# RTC.net
KiCad netlist of a schematic drawn in EAGLE
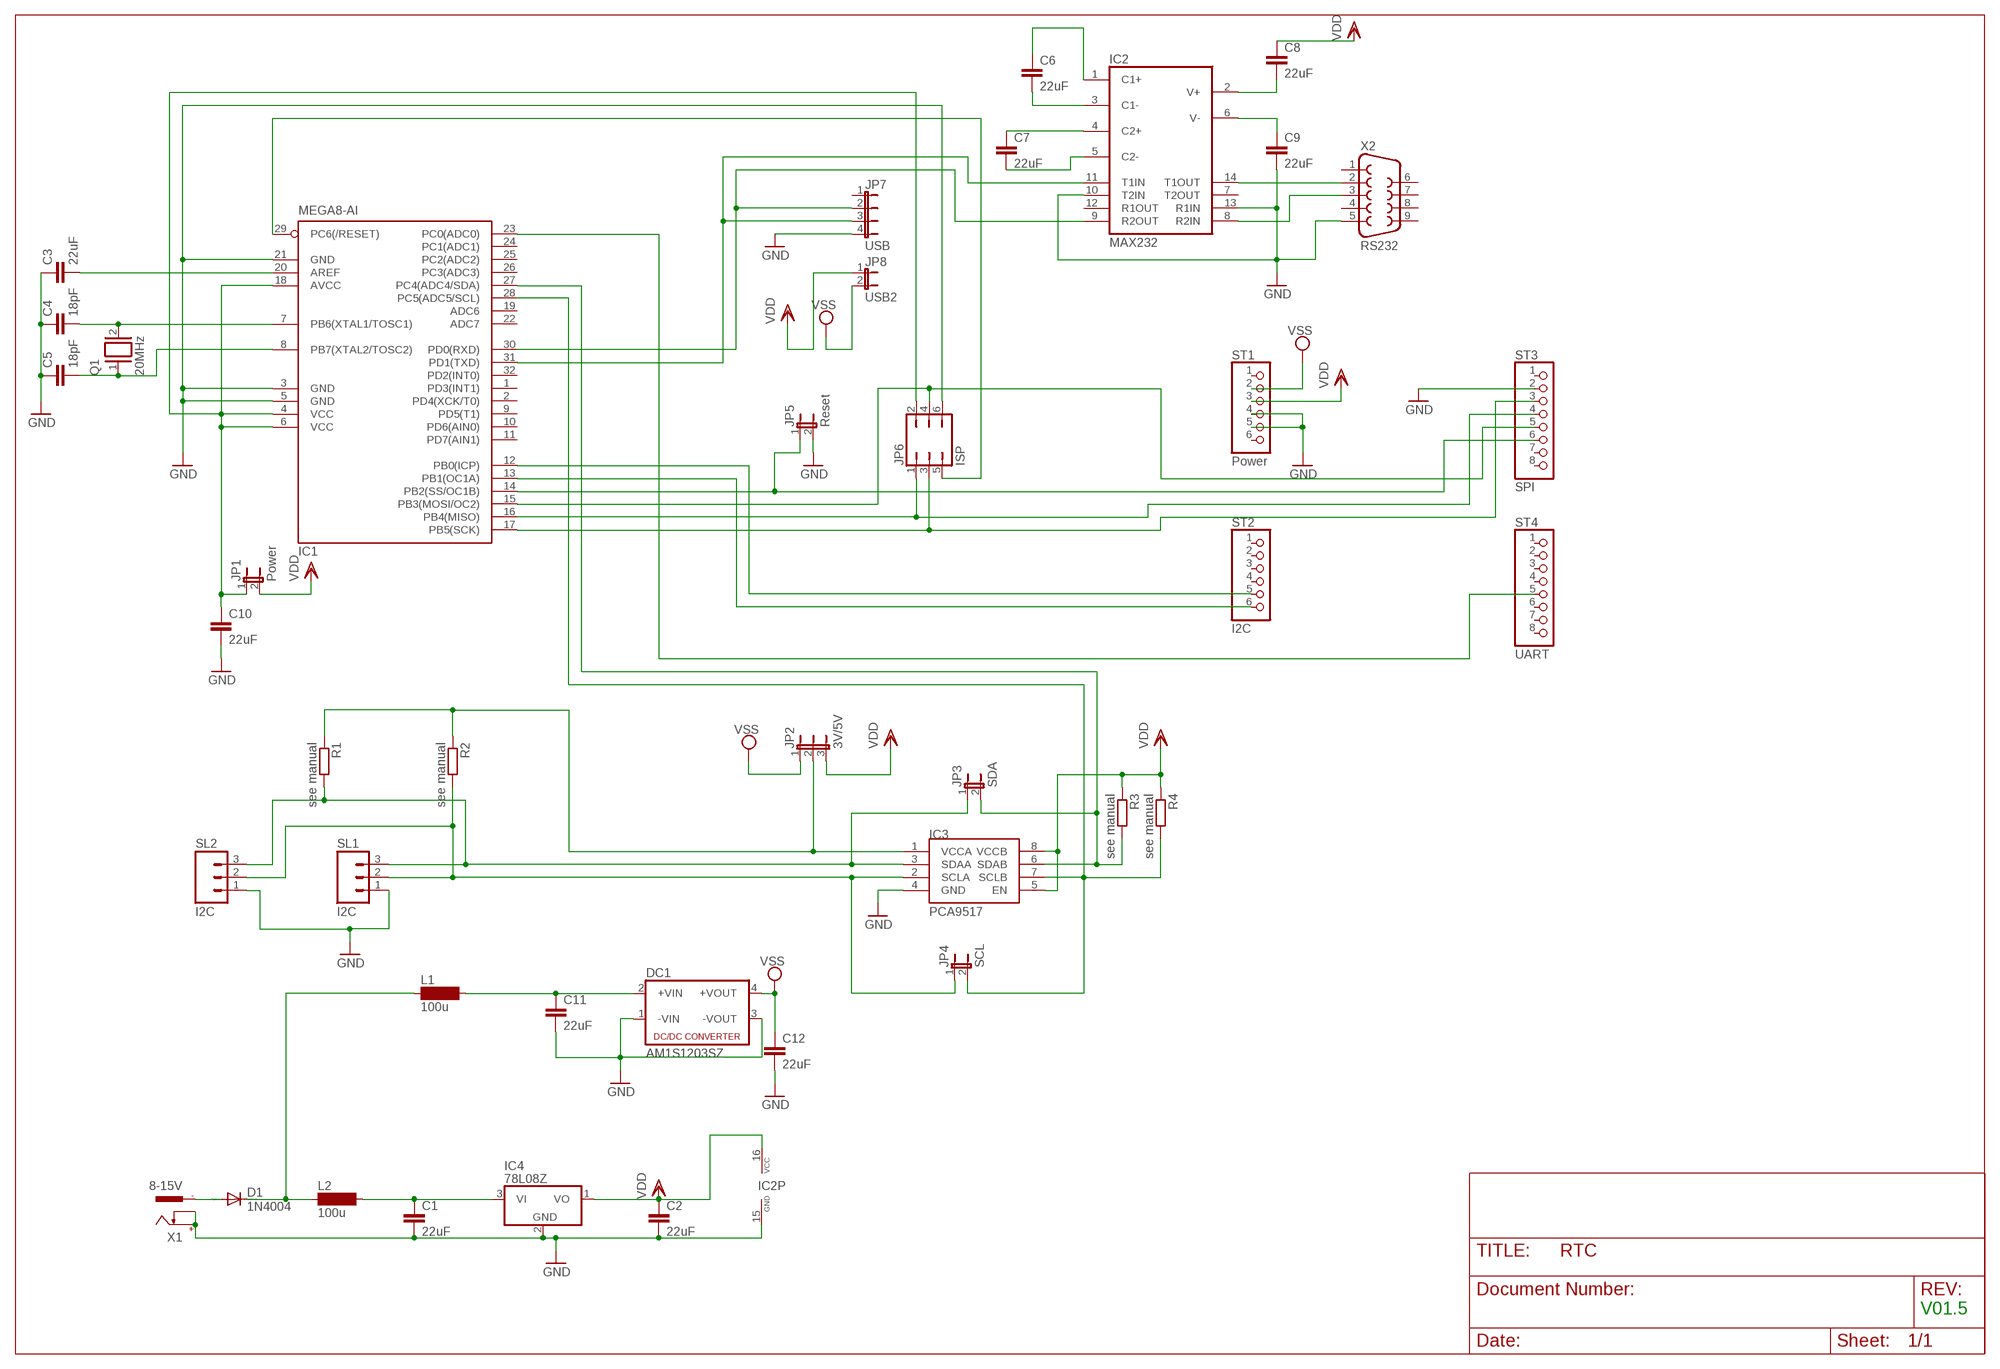
[diagram p0: schematic, sheet 1]

(export (version "E")
  (design (tool "Eeschema 10.0.6"))
  (components
    (comp (ref "C1")
      (value "22uF")
      (footprint "eagle-import:C1206")
      (libsource (lib "eagle-import") (part "C-EUC1206"))
    )
    (comp (ref "C2")
      (value "22uF")
      (footprint "eagle-import:C1206")
      (libsource (lib "eagle-import") (part "C-EUC1206"))
    )
    (comp (ref "C3")
      (value "22uF")
      (footprint "eagle-import:C1206")
      (libsource (lib "eagle-import") (part "C-EUC1206"))
    )
    (comp (ref "C4")
      (value "18pF")
      (footprint "eagle-import:C025-025X050")
      (libsource (lib "eagle-import") (part "resistor_C-EU025-025X050"))
    )
    (comp (ref "C5")
      (value "18pF")
      (footprint "eagle-import:C025-025X050")
      (libsource (lib "eagle-import") (part "resistor_C-EU025-025X050"))
    )
    (comp (ref "C6")
      (value "22uF")
      (footprint "eagle-import:C1206")
      (libsource (lib "eagle-import") (part "C-EUC1206"))
    )
    (comp (ref "C7")
      (value "22uF")
      (footprint "eagle-import:C1206")
      (libsource (lib "eagle-import") (part "C-EUC1206"))
    )
    (comp (ref "C8")
      (value "22uF")
      (footprint "eagle-import:C1206")
      (libsource (lib "eagle-import") (part "C-EUC1206"))
    )
    (comp (ref "C9")
      (value "22uF")
      (footprint "eagle-import:C1206")
      (libsource (lib "eagle-import") (part "C-EUC1206"))
    )
    (comp (ref "C10")
      (value "22uF")
      (footprint "eagle-import:C1206")
      (libsource (lib "eagle-import") (part "C-EUC1206"))
    )
    (comp (ref "C11")
      (value "22uF")
      (footprint "eagle-import:C1206")
      (libsource (lib "eagle-import") (part "C-EUC1206"))
    )
    (comp (ref "C12")
      (value "22uF")
      (footprint "eagle-import:C1206")
      (libsource (lib "eagle-import") (part "C-EUC1206"))
    )
    (comp (ref "D1")
      (value "1N4004")
      (footprint "eagle-import:DO41-10")
      (libsource (lib "eagle-import") (part "1N4004"))
    )
    (comp (ref "DC1")
      (value "AM1S1203SZ")
      (footprint "eagle-import:NME")
      (fields (field (name "MF") "C & D TECHNOLOGIES, INC") (field (name "MPN") "NME1205D"))
      (libsource (lib "eagle-import") (part "NME"))
    )
    (comp (ref "IC1")
      (value "MEGA8-AI")
      (footprint "eagle-import:TQFP32-08")
      (fields (field (name "MPN") "ATMEGA8-16AU"))
      (libsource (lib "eagle-import") (part "MEGA8-AI"))
    )
    (comp (ref "IC2")
      (value "MAX232")
      (footprint "eagle-import:DIL16")
      (fields (field (name "MF") "MAXIM") (field (name "MPN") "MAX232ACPE+"))
      (libsource (lib "eagle-import") (part "MAX232"))
    )
    (comp (ref "IC3")
      (value "PCA9517")
      (footprint "eagle-import:SO-08")
      (libsource (lib "eagle-import") (part "PCA9517"))
    )
    (comp (ref "IC4")
      (value "78L08Z")
      (footprint "eagle-import:TO92")
      (libsource (lib "eagle-import") (part "78ZL08"))
    )
    (comp (ref "JP1")
      (value "Power")
      (footprint "eagle-import:JP1")
      (libsource (lib "eagle-import") (part "JP1E"))
    )
    (comp (ref "JP2")
      (value "3V/5V")
      (footprint "eagle-import:JP2")
      (libsource (lib "eagle-import") (part "JP2E"))
    )
    (comp (ref "JP3")
      (value "SDA")
      (footprint "eagle-import:JP1")
      (libsource (lib "eagle-import") (part "JP1E"))
    )
    (comp (ref "JP4")
      (value "SCL")
      (footprint "eagle-import:JP1")
      (libsource (lib "eagle-import") (part "JP1E"))
    )
    (comp (ref "JP5")
      (value "Reset")
      (footprint "eagle-import:JP1")
      (libsource (lib "eagle-import") (part "JP1E"))
    )
    (comp (ref "JP6")
      (value "ISP")
      (footprint "eagle-import:JP3Q")
      (libsource (lib "eagle-import") (part "JP3Q"))
    )
    (comp (ref "JP7")
      (value "USB")
      (footprint "eagle-import:JP4")
      (libsource (lib "eagle-import") (part "JP4E"))
    )
    (comp (ref "JP8")
      (value "USB2")
      (footprint "eagle-import:JP1")
      (libsource (lib "eagle-import") (part "JP1E"))
    )
    (comp (ref "L1")
      (value "100u")
      (footprint "eagle-import:MS85")
      (libsource (lib "eagle-import") (part "MS85"))
    )
    (comp (ref "L2")
      (value "100u")
      (footprint "eagle-import:MS85")
      (libsource (lib "eagle-import") (part "MS85"))
    )
    (comp (ref "Q1")
      (value "20MHz")
      (footprint "eagle-import:QS")
      (libsource (lib "eagle-import") (part "XTAL/S"))
    )
    (comp (ref "R1")
      (value "see manual")
      (footprint "eagle-import:R1206")
      (libsource (lib "eagle-import") (part "R-EU_R1206"))
    )
    (comp (ref "R2")
      (value "see manual")
      (footprint "eagle-import:R1206")
      (libsource (lib "eagle-import") (part "R-EU_R1206"))
    )
    (comp (ref "R3")
      (value "see manual")
      (footprint "eagle-import:R1206")
      (libsource (lib "eagle-import") (part "R-EU_R1206"))
    )
    (comp (ref "R4")
      (value "see manual")
      (footprint "eagle-import:R1206")
      (libsource (lib "eagle-import") (part "R-EU_R1206"))
    )
    (comp (ref "SL1")
      (value "I2C")
      (footprint "eagle-import:03P")
      (libsource (lib "eagle-import") (part "M03"))
    )
    (comp (ref "SL2")
      (value "I2C")
      (footprint "eagle-import:03P")
      (libsource (lib "eagle-import") (part "M03"))
    )
    (comp (ref "ST1")
      (value "Power")
      (footprint "eagle-import:1X06")
      (libsource (lib "eagle-import") (part "PINHD-1X6"))
    )
    (comp (ref "ST2")
      (value "I2C")
      (footprint "eagle-import:1X06")
      (libsource (lib "eagle-import") (part "PINHD-1X6"))
    )
    (comp (ref "ST3")
      (value "SPI")
      (footprint "eagle-import:1X08")
      (libsource (lib "eagle-import") (part "PINHD-1X8"))
    )
    (comp (ref "ST4")
      (value "UART")
      (footprint "eagle-import:1X08")
      (libsource (lib "eagle-import") (part "PINHD-1X8"))
    )
    (comp (ref "X1")
      (value "8-15V")
      (footprint "eagle-import:737992-5")
      (libsource (lib "eagle-import") (part "737992-55"))
    )
    (comp (ref "X2")
      (value "RS232")
      (footprint "eagle-import:F09H")
      (libsource (lib "eagle-import") (part "F09H"))
    )
  )
  (nets
    (net (code "1") (name "GND") (class "Default")
      (node (ref "C1") (pin "2") (pinfunction "2_2") (pintype "passive"))
      (node (ref "C10") (pin "2") (pinfunction "2_2") (pintype "passive"))
      (node (ref "C11") (pin "2") (pinfunction "2_2") (pintype "passive"))
      (node (ref "C12") (pin "2") (pinfunction "2_2") (pintype "passive"))
      (node (ref "C2") (pin "2") (pinfunction "2_2") (pintype "passive"))
      (node (ref "C3") (pin "1") (pinfunction "1_1") (pintype "passive"))
      (node (ref "C4") (pin "1") (pinfunction "1_1") (pintype "passive"))
      (node (ref "C5") (pin "1") (pinfunction "1_1") (pintype "passive"))
      (node (ref "C9") (pin "2") (pinfunction "2_2") (pintype "passive"))
      (node (ref "DC1") (pin "1") (pinfunction "-VIN_1") (pintype "passive"))
      (node (ref "DC1") (pin "3") (pinfunction "-VOUT_3") (pintype "passive"))
      (node (ref "IC1") (pin "21") (pinfunction "GND_21") (pintype "power_in"))
      (node (ref "IC1") (pin "3") (pinfunction "GND_3") (pintype "power_in"))
      (node (ref "IC1") (pin "5") (pinfunction "GND_5") (pintype "power_in"))
      (node (ref "IC2") (pin "10") (pinfunction "T2IN_10") (pintype "input"))
      (node (ref "IC2") (pin "13") (pinfunction "R1IN_13") (pintype "input"))
      (node (ref "IC2") (pin "15") (pinfunction "GND_15") (pintype "power_in"))
      (node (ref "IC3") (pin "4") (pinfunction "GND_4") (pintype "bidirectional"))
      (node (ref "IC4") (pin "2") (pinfunction "GND_2") (pintype "passive"))
      (node (ref "JP5") (pin "2") (pinfunction "2_2") (pintype "passive"))
      (node (ref "JP6") (pin "6") (pinfunction "6_6") (pintype "passive"))
      (node (ref "JP7") (pin "4") (pinfunction "4_4") (pintype "passive"))
      (node (ref "SL1") (pin "1") (pinfunction "1_1") (pintype "passive"))
      (node (ref "SL2") (pin "1") (pinfunction "1_1") (pintype "passive"))
      (node (ref "ST1") (pin "4") (pinfunction "4_4") (pintype "passive"))
      (node (ref "ST1") (pin "5") (pinfunction "5_5") (pintype "passive"))
      (node (ref "ST3") (pin "2") (pinfunction "2_2") (pintype "passive"))
      (node (ref "X1") (pin "+") (pinfunction "+_+") (pintype "passive"))
      (node (ref "X1") (pin "K") (pinfunction "K_K") (pintype "passive"))
      (node (ref "X2") (pin "5") (pinfunction "5_5") (pintype "passive"))
    )
    (net (code "2") (name "Net-(D1-PadA)") (class "Default")
      (node (ref "D1") (pin "A") (pinfunction "A_A") (pintype "passive"))
      (node (ref "X1") (pin "-1") (pinfunction "-1_-1") (pintype "passive"))
    )
    (net (code "3") (name "Net-(D1-PadC)") (class "Default")
      (node (ref "D1") (pin "C") (pinfunction "C_C") (pintype "passive"))
      (node (ref "L1") (pin "1") (pinfunction "1_1") (pintype "passive"))
      (node (ref "L2") (pin "1") (pinfunction "1_1") (pintype "passive"))
    )
    (net (code "4") (name "Net-(DC1-+VIN)") (class "Default")
      (node (ref "C11") (pin "1") (pinfunction "1_1") (pintype "passive"))
      (node (ref "DC1") (pin "2") (pinfunction "+VIN_2") (pintype "passive"))
      (node (ref "L1") (pin "2") (pinfunction "2_2") (pintype "passive"))
    )
    (net (code "5") (name "Net-(IC1-AREF)") (class "Default")
      (node (ref "C3") (pin "2") (pinfunction "2_2") (pintype "passive"))
      (node (ref "IC1") (pin "20") (pinfunction "AREF_20") (pintype "passive"))
    )
    (net (code "6") (name "Net-(IC1-AVCC)") (class "Default")
      (node (ref "C10") (pin "1") (pinfunction "1_1") (pintype "passive"))
      (node (ref "IC1") (pin "18") (pinfunction "AVCC_18") (pintype "power_in"))
      (node (ref "IC1") (pin "4") (pinfunction "VCC_4") (pintype "power_in"))
      (node (ref "IC1") (pin "6") (pinfunction "VCC_6") (pintype "power_in"))
      (node (ref "JP1") (pin "1") (pinfunction "1_1") (pintype "passive"))
      (node (ref "JP6") (pin "2") (pinfunction "2_2") (pintype "passive"))
    )
    (net (code "7") (name "Net-(IC1-PB0(ICP))") (class "Default")
      (node (ref "IC1") (pin "12") (pinfunction "PB0(ICP)_12") (pintype "bidirectional"))
      (node (ref "ST2") (pin "5") (pinfunction "5_5") (pintype "passive"))
    )
    (net (code "8") (name "Net-(IC1-PB1(OC1A))") (class "Default")
      (node (ref "IC1") (pin "13") (pinfunction "PB1(OC1A)_13") (pintype "bidirectional"))
      (node (ref "ST2") (pin "6") (pinfunction "6_6") (pintype "passive"))
    )
    (net (code "9") (name "Net-(IC1-PB2(SS{slash}OC1B))") (class "Default")
      (node (ref "IC1") (pin "14") (pinfunction "PB2(SS/OC1B)_14") (pintype "bidirectional"))
      (node (ref "JP5") (pin "1") (pinfunction "1_1") (pintype "passive"))
      (node (ref "ST3") (pin "6") (pinfunction "6_6") (pintype "passive"))
    )
    (net (code "10") (name "Net-(IC1-PB3(MOSI{slash}OC2))") (class "Default")
      (node (ref "IC1") (pin "15") (pinfunction "PB3(MOSI/OC2)_15") (pintype "bidirectional"))
      (node (ref "JP6") (pin "4") (pinfunction "4_4") (pintype "passive"))
      (node (ref "ST3") (pin "5") (pinfunction "5_5") (pintype "passive"))
    )
    (net (code "11") (name "Net-(IC1-PB4(MISO))") (class "Default")
      (node (ref "IC1") (pin "16") (pinfunction "PB4(MISO)_16") (pintype "bidirectional"))
      (node (ref "JP6") (pin "1") (pinfunction "1_1") (pintype "passive"))
      (node (ref "ST3") (pin "4") (pinfunction "4_4") (pintype "passive"))
    )
    (net (code "12") (name "Net-(IC1-PB5(SCK))") (class "Default")
      (node (ref "IC1") (pin "17") (pinfunction "PB5(SCK)_17") (pintype "bidirectional"))
      (node (ref "JP6") (pin "3") (pinfunction "3_3") (pintype "passive"))
      (node (ref "ST3") (pin "3") (pinfunction "3_3") (pintype "passive"))
    )
    (net (code "13") (name "Net-(IC1-PB6(XTAL1{slash}TOSC1))") (class "Default")
      (node (ref "C4") (pin "2") (pinfunction "2_2") (pintype "passive"))
      (node (ref "IC1") (pin "7") (pinfunction "PB6(XTAL1/TOSC1)_7") (pintype "bidirectional"))
      (node (ref "Q1") (pin "2") (pinfunction "2_2") (pintype "passive"))
    )
    (net (code "14") (name "Net-(IC1-PB7(XTAL2{slash}TOSC2))") (class "Default")
      (node (ref "C5") (pin "2") (pinfunction "2_2") (pintype "passive"))
      (node (ref "IC1") (pin "8") (pinfunction "PB7(XTAL2/TOSC2)_8") (pintype "bidirectional"))
      (node (ref "Q1") (pin "1") (pinfunction "1_1") (pintype "passive"))
    )
    (net (code "15") (name "Net-(IC1-PC0(ADC0))") (class "Default")
      (node (ref "IC1") (pin "23") (pinfunction "PC0(ADC0)_23") (pintype "bidirectional"))
      (node (ref "ST4") (pin "5") (pinfunction "5_5") (pintype "passive"))
    )
    (net (code "16") (name "Net-(IC1-PC4(ADC4{slash}SDA))") (class "Default")
      (node (ref "IC1") (pin "27") (pinfunction "PC4(ADC4/SDA)_27") (pintype "bidirectional"))
      (node (ref "IC3") (pin "6") (pinfunction "SDAB_6") (pintype "bidirectional"))
      (node (ref "JP3") (pin "2") (pinfunction "2_2") (pintype "passive"))
      (node (ref "R3") (pin "2") (pinfunction "2_2") (pintype "passive"))
    )
    (net (code "17") (name "Net-(IC1-PC5(ADC5{slash}SCL))") (class "Default")
      (node (ref "IC1") (pin "28") (pinfunction "PC5(ADC5/SCL)_28") (pintype "bidirectional"))
      (node (ref "IC3") (pin "7") (pinfunction "SCLB_7") (pintype "bidirectional"))
      (node (ref "JP4") (pin "2") (pinfunction "2_2") (pintype "passive"))
      (node (ref "R4") (pin "2") (pinfunction "2_2") (pintype "passive"))
    )
    (net (code "18") (name "Net-(IC1-PC6({slash}RESET))") (class "Default")
      (node (ref "IC1") (pin "29") (pinfunction "PC6(/RESET)_29") (pintype "bidirectional"))
      (node (ref "JP6") (pin "5") (pinfunction "5_5") (pintype "passive"))
    )
    (net (code "19") (name "Net-(IC1-PD0(RXD))") (class "Default")
      (node (ref "IC1") (pin "30") (pinfunction "PD0(RXD)_30") (pintype "bidirectional"))
      (node (ref "IC2") (pin "9") (pinfunction "R2OUT_9") (pintype "output"))
      (node (ref "JP7") (pin "2") (pinfunction "2_2") (pintype "passive"))
    )
    (net (code "20") (name "Net-(IC1-PD1(TXD))") (class "Default")
      (node (ref "IC1") (pin "31") (pinfunction "PD1(TXD)_31") (pintype "bidirectional"))
      (node (ref "IC2") (pin "11") (pinfunction "T1IN_11") (pintype "input"))
      (node (ref "JP7") (pin "3") (pinfunction "3_3") (pintype "passive"))
    )
    (net (code "21") (name "Net-(IC2A-C1+)") (class "Default")
      (node (ref "C6") (pin "1") (pinfunction "1_1") (pintype "passive"))
      (node (ref "IC2") (pin "1") (pinfunction "C1+_1") (pintype "bidirectional"))
    )
    (net (code "22") (name "Net-(IC2A-C1-)") (class "Default")
      (node (ref "C6") (pin "2") (pinfunction "2_2") (pintype "passive"))
      (node (ref "IC2") (pin "3") (pinfunction "C1-_3") (pintype "bidirectional"))
    )
    (net (code "23") (name "Net-(IC2A-C2+)") (class "Default")
      (node (ref "C7") (pin "1") (pinfunction "1_1") (pintype "passive"))
      (node (ref "IC2") (pin "4") (pinfunction "C2+_4") (pintype "bidirectional"))
    )
    (net (code "24") (name "Net-(IC2A-C2-)") (class "Default")
      (node (ref "C7") (pin "2") (pinfunction "2_2") (pintype "passive"))
      (node (ref "IC2") (pin "5") (pinfunction "C2-_5") (pintype "bidirectional"))
    )
    (net (code "25") (name "Net-(IC2A-R2IN)") (class "Default")
      (node (ref "IC2") (pin "8") (pinfunction "R2IN_8") (pintype "input"))
      (node (ref "X2") (pin "3") (pinfunction "3_3") (pintype "passive"))
    )
    (net (code "26") (name "Net-(IC2A-T1OUT)") (class "Default")
      (node (ref "IC2") (pin "14") (pinfunction "T1OUT_14") (pintype "output"))
      (node (ref "X2") (pin "2") (pinfunction "2_2") (pintype "passive"))
    )
    (net (code "27") (name "Net-(IC2A-V+)") (class "Default")
      (node (ref "C8") (pin "2") (pinfunction "2_2") (pintype "passive"))
      (node (ref "IC2") (pin "2") (pinfunction "V+_2") (pintype "bidirectional"))
    )
    (net (code "28") (name "Net-(IC2A-V-)") (class "Default")
      (node (ref "C9") (pin "1") (pinfunction "1_1") (pintype "passive"))
      (node (ref "IC2") (pin "6") (pinfunction "V-_6") (pintype "bidirectional"))
    )
    (net (code "29") (name "Net-(IC3-SCLA)") (class "Default")
      (node (ref "IC3") (pin "2") (pinfunction "SCLA_2") (pintype "bidirectional"))
      (node (ref "JP4") (pin "1") (pinfunction "1_1") (pintype "passive"))
      (node (ref "R2") (pin "2") (pinfunction "2_2") (pintype "passive"))
      (node (ref "SL1") (pin "2") (pinfunction "2_2") (pintype "passive"))
      (node (ref "SL2") (pin "2") (pinfunction "2_2") (pintype "passive"))
    )
    (net (code "30") (name "Net-(IC3-SDAA)") (class "Default")
      (node (ref "IC3") (pin "3") (pinfunction "SDAA_3") (pintype "bidirectional"))
      (node (ref "JP3") (pin "1") (pinfunction "1_1") (pintype "passive"))
      (node (ref "R1") (pin "2") (pinfunction "2_2") (pintype "passive"))
      (node (ref "SL1") (pin "3") (pinfunction "3_3") (pintype "passive"))
      (node (ref "SL2") (pin "3") (pinfunction "3_3") (pintype "passive"))
    )
    (net (code "31") (name "Net-(IC3-VCCA)") (class "Default")
      (node (ref "IC3") (pin "1") (pinfunction "VCCA_1") (pintype "bidirectional"))
      (node (ref "JP2") (pin "2") (pinfunction "2_2") (pintype "passive"))
      (node (ref "R1") (pin "1") (pinfunction "1_1") (pintype "passive"))
      (node (ref "R2") (pin "1") (pinfunction "1_1") (pintype "passive"))
    )
    (net (code "32") (name "Net-(IC4-VI)") (class "Default")
      (node (ref "C1") (pin "1") (pinfunction "1_1") (pintype "passive"))
      (node (ref "IC4") (pin "3") (pinfunction "VI_3") (pintype "input"))
      (node (ref "L2") (pin "2") (pinfunction "2_2") (pintype "passive"))
    )
    (net (code "33") (name "VDD") (class "Default")
      (node (ref "C2") (pin "1") (pinfunction "1_1") (pintype "passive"))
      (node (ref "C8") (pin "1") (pinfunction "1_1") (pintype "passive"))
      (node (ref "IC2") (pin "16") (pinfunction "VCC_16") (pintype "power_in"))
      (node (ref "IC3") (pin "5") (pinfunction "EN_5") (pintype "bidirectional"))
      (node (ref "IC3") (pin "8") (pinfunction "VCCB_8") (pintype "bidirectional"))
      (node (ref "IC4") (pin "1") (pinfunction "VO_1") (pintype "passive"))
      (node (ref "JP1") (pin "2") (pinfunction "2_2") (pintype "passive"))
      (node (ref "JP2") (pin "3") (pinfunction "3_3") (pintype "passive"))
      (node (ref "JP8") (pin "1") (pinfunction "1_1") (pintype "passive"))
      (node (ref "R3") (pin "1") (pinfunction "1_1") (pintype "passive"))
      (node (ref "R4") (pin "1") (pinfunction "1_1") (pintype "passive"))
      (node (ref "ST1") (pin "3") (pinfunction "3_3") (pintype "passive"))
    )
    (net (code "34") (name "VSS") (class "Default")
      (node (ref "C12") (pin "1") (pinfunction "1_1") (pintype "passive"))
      (node (ref "DC1") (pin "4") (pinfunction "+VOUT_4") (pintype "passive"))
      (node (ref "JP2") (pin "1") (pinfunction "1_1") (pintype "passive"))
      (node (ref "JP8") (pin "2") (pinfunction "2_2") (pintype "passive"))
      (node (ref "ST1") (pin "2") (pinfunction "2_2") (pintype "passive"))
    )
    (net (code "35") (name "unconnected-(IC1-ADC6-Pad19)") (class "Default")
      (node (ref "IC1") (pin "19") (pinfunction "ADC6_19") (pintype "bidirectional"))
    )
    (net (code "36") (name "unconnected-(IC1-ADC7-Pad22)") (class "Default")
      (node (ref "IC1") (pin "22") (pinfunction "ADC7_22") (pintype "bidirectional"))
    )
    (net (code "37") (name "unconnected-(IC1-PC1(ADC1)-Pad24)") (class "Default")
      (node (ref "IC1") (pin "24") (pinfunction "PC1(ADC1)_24") (pintype "bidirectional"))
    )
    (net (code "38") (name "unconnected-(IC1-PC2(ADC2)-Pad25)") (class "Default")
      (node (ref "IC1") (pin "25") (pinfunction "PC2(ADC2)_25") (pintype "bidirectional"))
    )
    (net (code "39") (name "unconnected-(IC1-PC3(ADC3)-Pad26)") (class "Default")
      (node (ref "IC1") (pin "26") (pinfunction "PC3(ADC3)_26") (pintype "bidirectional"))
    )
    (net (code "40") (name "unconnected-(IC1-PD2(INT0)-Pad32)") (class "Default")
      (node (ref "IC1") (pin "32") (pinfunction "PD2(INT0)_32") (pintype "bidirectional"))
    )
    (net (code "41") (name "unconnected-(IC1-PD3(INT1)-Pad1)") (class "Default")
      (node (ref "IC1") (pin "1") (pinfunction "PD3(INT1)_1") (pintype "bidirectional"))
    )
    (net (code "42") (name "unconnected-(IC1-PD4(XCK{slash}T0)-Pad2)") (class "Default")
      (node (ref "IC1") (pin "2") (pinfunction "PD4(XCK/T0)_2") (pintype "bidirectional"))
    )
    (net (code "43") (name "unconnected-(IC1-PD5(T1)-Pad9)") (class "Default")
      (node (ref "IC1") (pin "9") (pinfunction "PD5(T1)_9") (pintype "bidirectional"))
    )
    (net (code "44") (name "unconnected-(IC1-PD6(AIN0)-Pad10)") (class "Default")
      (node (ref "IC1") (pin "10") (pinfunction "PD6(AIN0)_10") (pintype "bidirectional"))
    )
    (net (code "45") (name "unconnected-(IC1-PD7(AIN1)-Pad11)") (class "Default")
      (node (ref "IC1") (pin "11") (pinfunction "PD7(AIN1)_11") (pintype "bidirectional"))
    )
    (net (code "46") (name "unconnected-(IC2A-R1OUT-Pad12)") (class "Default")
      (node (ref "IC2") (pin "12") (pinfunction "R1OUT_12") (pintype "output"))
    )
    (net (code "47") (name "unconnected-(IC2A-T2OUT-Pad7)") (class "Default")
      (node (ref "IC2") (pin "7") (pinfunction "T2OUT_7") (pintype "output"))
    )
    (net (code "48") (name "unconnected-(JP7-Pad1)") (class "Default")
      (node (ref "JP7") (pin "1") (pinfunction "1_1") (pintype "passive"))
    )
    (net (code "49") (name "unconnected-(ST1-Pad1)") (class "Default")
      (node (ref "ST1") (pin "1") (pinfunction "1_1") (pintype "passive"))
    )
    (net (code "50") (name "unconnected-(ST1-Pad6)") (class "Default")
      (node (ref "ST1") (pin "6") (pinfunction "6_6") (pintype "passive"))
    )
    (net (code "51") (name "unconnected-(ST2-Pad1)") (class "Default")
      (node (ref "ST2") (pin "1") (pinfunction "1_1") (pintype "passive"))
    )
    (net (code "52") (name "unconnected-(ST2-Pad2)") (class "Default")
      (node (ref "ST2") (pin "2") (pinfunction "2_2") (pintype "passive"))
    )
    (net (code "53") (name "unconnected-(ST2-Pad3)") (class "Default")
      (node (ref "ST2") (pin "3") (pinfunction "3_3") (pintype "passive"))
    )
    (net (code "54") (name "unconnected-(ST2-Pad4)") (class "Default")
      (node (ref "ST2") (pin "4") (pinfunction "4_4") (pintype "passive"))
    )
    (net (code "55") (name "unconnected-(ST3-Pad1)") (class "Default")
      (node (ref "ST3") (pin "1") (pinfunction "1_1") (pintype "passive"))
    )
    (net (code "56") (name "unconnected-(ST3-Pad7)") (class "Default")
      (node (ref "ST3") (pin "7") (pinfunction "7_7") (pintype "passive"))
    )
    (net (code "57") (name "unconnected-(ST3-Pad8)") (class "Default")
      (node (ref "ST3") (pin "8") (pinfunction "8_8") (pintype "passive"))
    )
    (net (code "58") (name "unconnected-(ST4-Pad1)") (class "Default")
      (node (ref "ST4") (pin "1") (pinfunction "1_1") (pintype "passive"))
    )
    (net (code "59") (name "unconnected-(ST4-Pad2)") (class "Default")
      (node (ref "ST4") (pin "2") (pinfunction "2_2") (pintype "passive"))
    )
    (net (code "60") (name "unconnected-(ST4-Pad3)") (class "Default")
      (node (ref "ST4") (pin "3") (pinfunction "3_3") (pintype "passive"))
    )
    (net (code "61") (name "unconnected-(ST4-Pad4)") (class "Default")
      (node (ref "ST4") (pin "4") (pinfunction "4_4") (pintype "passive"))
    )
    (net (code "62") (name "unconnected-(ST4-Pad6)") (class "Default")
      (node (ref "ST4") (pin "6") (pinfunction "6_6") (pintype "passive"))
    )
    (net (code "63") (name "unconnected-(ST4-Pad7)") (class "Default")
      (node (ref "ST4") (pin "7") (pinfunction "7_7") (pintype "passive"))
    )
    (net (code "64") (name "unconnected-(ST4-Pad8)") (class "Default")
      (node (ref "ST4") (pin "8") (pinfunction "8_8") (pintype "passive"))
    )
    (net (code "65") (name "unconnected-(X1-Pad-2)") (class "Default")
      (node (ref "X1") (pin "-2") (pinfunction "-2_-2") (pintype "passive"))
    )
    (net (code "66") (name "unconnected-(X2-Pad1)") (class "Default")
      (node (ref "X2") (pin "1") (pinfunction "1_1") (pintype "passive"))
    )
    (net (code "67") (name "unconnected-(X2-Pad4)") (class "Default")
      (node (ref "X2") (pin "4") (pinfunction "4_4") (pintype "passive"))
    )
    (net (code "68") (name "unconnected-(X2-Pad6)") (class "Default")
      (node (ref "X2") (pin "6") (pinfunction "6_6") (pintype "passive"))
    )
    (net (code "69") (name "unconnected-(X2-Pad7)") (class "Default")
      (node (ref "X2") (pin "7") (pinfunction "7_7") (pintype "passive"))
    )
    (net (code "70") (name "unconnected-(X2-Pad8)") (class "Default")
      (node (ref "X2") (pin "8") (pinfunction "8_8") (pintype "passive"))
    )
    (net (code "71") (name "unconnected-(X2-Pad9)") (class "Default")
      (node (ref "X2") (pin "9") (pinfunction "9_9") (pintype "passive"))
    )
  )
)
